# SmartSensorWifi.net
KiCad netlist of a schematic drawn in EAGLE
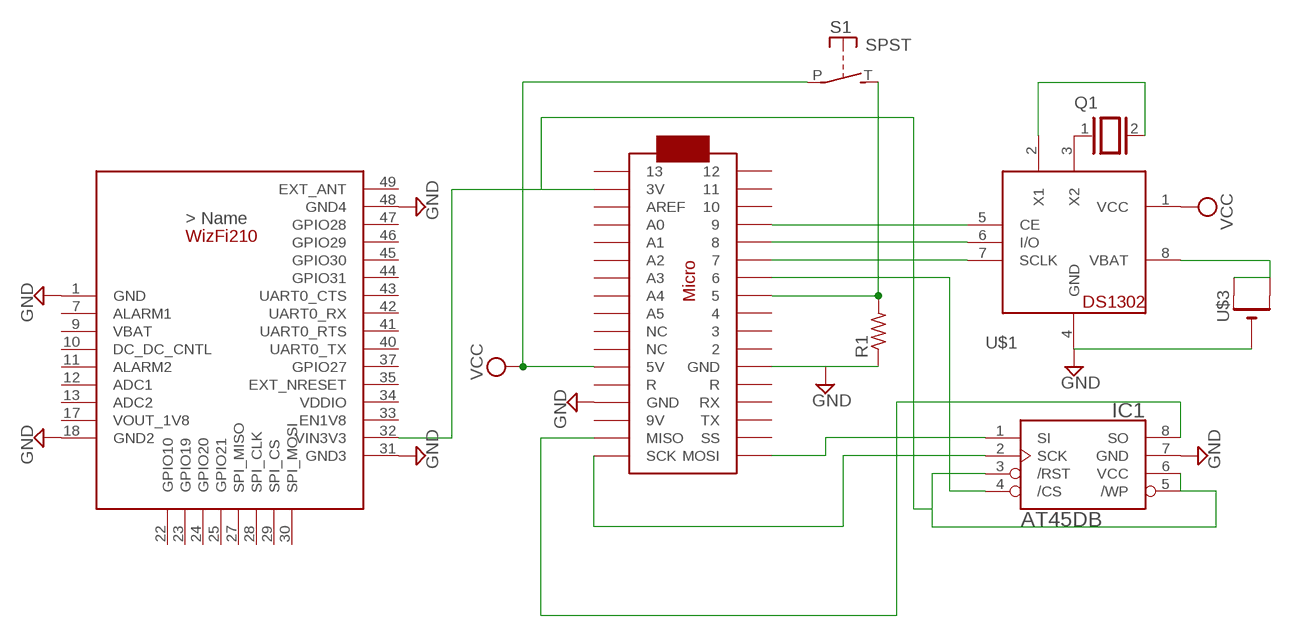
[diagram p0: schematic, sheet 1]

(export (version "E")
  (design (tool "Eeschema 10.0.6"))
  (components
    (comp (ref "IC1")
      (value "AT45DB-S")
      (footprint "eagle-import:SOIC8_208MIL")
      (libsource (lib "eagle-import") (part "AT45DB-S"))
    )
    (comp (ref "Q1")
      (value "XTAL")
      (footprint "eagle-import:Q")
      (libsource (lib "eagle-import") (part "XTAL"))
    )
    (comp (ref "R1")
      (value "FLIPFLOP-RES")
      (footprint "eagle-import:0805-THM")
      (libsource (lib "eagle-import") (part "FLIPFLOP-RES"))
    )
    (comp (ref "S1")
      (value "SPST")
      (footprint "eagle-import:JUDCOSPST")
      (libsource (lib "eagle-import") (part "SPST"))
    )
    (comp (ref "U$1")
      (value "DS1302")
      (footprint "eagle-import:DIL08-ROUND")
      (libsource (lib "eagle-import") (part "DS1302"))
    )
    (comp (ref "U$2")
      (value "ARDUINOMICRO")
      (footprint "eagle-import:ARDUINOMICRO")
      (libsource (lib "eagle-import") (part "ARDUINOMICRO"))
    )
    (comp (ref "U$3")
      (value "CR2032THM")
      (footprint "eagle-import:CR2032-THRU")
      (libsource (lib "eagle-import") (part "CR2032THM"))
    )
    (comp (ref "WIFI1")
      (value "WIZFI210")
      (footprint "eagle-import:WIZFI210")
      (libsource (lib "eagle-import") (part "WIZFI210"))
    )
  )
  (nets
    (net (code "1") (name "/VBAT") (class "Default")
      (node (ref "WIFI1") (pin "9") (pinfunction "VBAT_9") (pintype "power_in"))
    )
    (net (code "2") (name "/VOUT_1V8") (class "Default")
      (node (ref "WIFI1") (pin "17") (pinfunction "VOUT_1V8_17") (pintype "power_in"))
    )
    (net (code "3") (name "GND") (class "Default")
      (node (ref "IC1") (pin "7") (pinfunction "GND_7") (pintype "power_in"))
      (node (ref "R1") (pin "1") (pinfunction "1_1") (pintype "passive"))
      (node (ref "U$1") (pin "4") (pinfunction "GND_4") (pintype "power_in"))
      (node (ref "U$2") (pin "P$12") (pinfunction "GND_P$12") (pintype "bidirectional"))
      (node (ref "U$2") (pin "P$21") (pinfunction "GND_P$21") (pintype "bidirectional"))
      (node (ref "U$3") (pin "-") (pinfunction "-_-") (pintype "passive"))
      (node (ref "WIFI1") (pin "1") (pinfunction "GND_1") (pintype "power_in"))
      (node (ref "WIFI1") (pin "18") (pinfunction "GND2_18") (pintype "power_in"))
      (node (ref "WIFI1") (pin "31") (pinfunction "GND3_31") (pintype "power_in"))
      (node (ref "WIFI1") (pin "48") (pinfunction "GND4_48") (pintype "power_in"))
    )
    (net (code "4") (name "Net-(IC1-SCK)") (class "Default")
      (node (ref "IC1") (pin "2") (pinfunction "SCK_2") (pintype "input"))
      (node (ref "U$2") (pin "P$18") (pinfunction "SCK_P$18") (pintype "bidirectional"))
    )
    (net (code "5") (name "Net-(IC1-SI)") (class "Default")
      (node (ref "IC1") (pin "1") (pinfunction "SI_1") (pintype "input"))
      (node (ref "U$2") (pin "P$17") (pinfunction "MOSI_P$17") (pintype "bidirectional"))
    )
    (net (code "6") (name "Net-(IC1-SO)") (class "Default")
      (node (ref "IC1") (pin "8") (pinfunction "SO_8") (pintype "output"))
      (node (ref "U$2") (pin "P$19") (pinfunction "MISO_P$19") (pintype "bidirectional"))
    )
    (net (code "7") (name "Net-(IC1-VCC)") (class "Default")
      (node (ref "IC1") (pin "3") (pinfunction "/RST_3") (pintype "input"))
      (node (ref "IC1") (pin "5") (pinfunction "/WP_5") (pintype "input"))
      (node (ref "IC1") (pin "6") (pinfunction "VCC_6") (pintype "power_in"))
      (node (ref "U$2") (pin "P$33") (pinfunction "3V_P$33") (pintype "bidirectional"))
      (node (ref "WIFI1") (pin "32") (pinfunction "VIN3V3_32") (pintype "power_in"))
    )
    (net (code "8") (name "Net-(IC1-{slash}CS)") (class "Default")
      (node (ref "IC1") (pin "4") (pinfunction "/CS_4") (pintype "input"))
      (node (ref "U$2") (pin "P$7") (pinfunction "6_P$7") (pintype "bidirectional"))
    )
    (net (code "9") (name "Net-(S1-S)") (class "Default")
      (node (ref "R1") (pin "2") (pinfunction "2_2") (pintype "passive"))
      (node (ref "S1") (pin "T") (pinfunction "S_T") (pintype "passive"))
      (node (ref "U$2") (pin "P$8") (pinfunction "5_P$8") (pintype "bidirectional"))
    )
    (net (code "10") (name "Net-(U$1-CE)") (class "Default")
      (node (ref "U$1") (pin "5") (pinfunction "CE_5") (pintype "input"))
      (node (ref "U$2") (pin "P$4") (pinfunction "9_P$4") (pintype "bidirectional"))
    )
    (net (code "11") (name "Net-(U$1-I{slash}O)") (class "Default")
      (node (ref "U$1") (pin "6") (pinfunction "I/O_6") (pintype "bidirectional"))
      (node (ref "U$2") (pin "P$5") (pinfunction "8_P$5") (pintype "bidirectional"))
    )
    (net (code "12") (name "Net-(U$1-SCLK)") (class "Default")
      (node (ref "U$1") (pin "7") (pinfunction "SCLK_7") (pintype "input"))
      (node (ref "U$2") (pin "P$6") (pinfunction "7_P$6") (pintype "bidirectional"))
    )
    (net (code "13") (name "Net-(U$1-VBAT)") (class "Default")
      (node (ref "U$1") (pin "8") (pinfunction "VBAT_8") (pintype "power_in"))
      (node (ref "U$3") (pin "+1") (pinfunction "+_+1") (pintype "passive"))
      (node (ref "U$3") (pin "+2") (pinfunction "+1_+2") (pintype "passive"))
    )
    (net (code "14") (name "Net-(U$1-X1)") (class "Default")
      (node (ref "Q1") (pin "2") (pinfunction "2_2") (pintype "passive"))
      (node (ref "U$1") (pin "2") (pinfunction "X1_2") (pintype "passive"))
    )
    (net (code "15") (name "Net-(U$1-X2)") (class "Default")
      (node (ref "Q1") (pin "1") (pinfunction "1_1") (pintype "passive"))
      (node (ref "U$1") (pin "3") (pinfunction "X2_3") (pintype "passive"))
    )
    (net (code "16") (name "VCC") (class "Default")
      (node (ref "S1") (pin "P") (pinfunction "P_P") (pintype "passive"))
      (node (ref "U$1") (pin "1") (pinfunction "VCC_1") (pintype "power_in"))
      (node (ref "U$2") (pin "P$23") (pinfunction "5V_P$23") (pintype "bidirectional"))
    )
    (net (code "17") (name "unconnected-(U$2-2-PadP$11)") (class "Default")
      (node (ref "U$2") (pin "P$11") (pinfunction "2_P$11") (pintype "bidirectional"))
    )
    (net (code "18") (name "unconnected-(U$2-3-PadP$10)") (class "Default")
      (node (ref "U$2") (pin "P$10") (pinfunction "3_P$10") (pintype "bidirectional"))
    )
    (net (code "19") (name "unconnected-(U$2-4-PadP$9)") (class "Default")
      (node (ref "U$2") (pin "P$9") (pinfunction "4_P$9") (pintype "bidirectional"))
    )
    (net (code "20") (name "unconnected-(U$2-9V-PadP$20)") (class "Default")
      (node (ref "U$2") (pin "P$20") (pinfunction "9V_P$20") (pintype "bidirectional"))
    )
    (net (code "21") (name "unconnected-(U$2-10-PadP$3)") (class "Default")
      (node (ref "U$2") (pin "P$3") (pinfunction "10_P$3") (pintype "bidirectional"))
    )
    (net (code "22") (name "unconnected-(U$2-11-PadP$2)") (class "Default")
      (node (ref "U$2") (pin "P$2") (pinfunction "11_P$2") (pintype "bidirectional"))
    )
    (net (code "23") (name "unconnected-(U$2-12-PadP$1)") (class "Default")
      (node (ref "U$2") (pin "P$1") (pinfunction "12_P$1") (pintype "bidirectional"))
    )
    (net (code "24") (name "unconnected-(U$2-13-PadP$34)") (class "Default")
      (node (ref "U$2") (pin "P$34") (pinfunction "13_P$34") (pintype "bidirectional"))
    )
    (net (code "25") (name "unconnected-(U$2-A0-PadP$31)") (class "Default")
      (node (ref "U$2") (pin "P$31") (pinfunction "A0_P$31") (pintype "bidirectional"))
    )
    (net (code "26") (name "unconnected-(U$2-A1-PadP$30)") (class "Default")
      (node (ref "U$2") (pin "P$30") (pinfunction "A1_P$30") (pintype "bidirectional"))
    )
    (net (code "27") (name "unconnected-(U$2-A2-PadP$29)") (class "Default")
      (node (ref "U$2") (pin "P$29") (pinfunction "A2_P$29") (pintype "bidirectional"))
    )
    (net (code "28") (name "unconnected-(U$2-A3-PadP$28)") (class "Default")
      (node (ref "U$2") (pin "P$28") (pinfunction "A3_P$28") (pintype "bidirectional"))
    )
    (net (code "29") (name "unconnected-(U$2-A4-PadP$27)") (class "Default")
      (node (ref "U$2") (pin "P$27") (pinfunction "A4_P$27") (pintype "bidirectional"))
    )
    (net (code "30") (name "unconnected-(U$2-A5-PadP$26)") (class "Default")
      (node (ref "U$2") (pin "P$26") (pinfunction "A5_P$26") (pintype "bidirectional"))
    )
    (net (code "31") (name "unconnected-(U$2-AREF-PadP$32)") (class "Default")
      (node (ref "U$2") (pin "P$32") (pinfunction "AREF_P$32") (pintype "bidirectional"))
    )
    (net (code "32") (name "unconnected-(U$2-NC-PadP$24)") (class "Default")
      (node (ref "U$2") (pin "P$24") (pinfunction "NC_P$24") (pintype "bidirectional"))
    )
    (net (code "33") (name "unconnected-(U$2-NC-PadP$25)") (class "Default")
      (node (ref "U$2") (pin "P$25") (pinfunction "NC_P$25") (pintype "bidirectional"))
    )
    (net (code "34") (name "unconnected-(U$2-R-PadP$13)") (class "Default")
      (node (ref "U$2") (pin "P$13") (pinfunction "R_P$13") (pintype "bidirectional"))
    )
    (net (code "35") (name "unconnected-(U$2-R-PadP$22)") (class "Default")
      (node (ref "U$2") (pin "P$22") (pinfunction "R_P$22") (pintype "bidirectional"))
    )
    (net (code "36") (name "unconnected-(U$2-RX-PadP$14)") (class "Default")
      (node (ref "U$2") (pin "P$14") (pinfunction "RX_P$14") (pintype "bidirectional"))
    )
    (net (code "37") (name "unconnected-(U$2-SS-PadP$16)") (class "Default")
      (node (ref "U$2") (pin "P$16") (pinfunction "SS_P$16") (pintype "bidirectional"))
    )
    (net (code "38") (name "unconnected-(U$2-TX-PadP$15)") (class "Default")
      (node (ref "U$2") (pin "P$15") (pinfunction "TX_P$15") (pintype "bidirectional"))
    )
    (net (code "39") (name "unconnected-(WIFI1-ADC1-Pad12)") (class "Default")
      (node (ref "WIFI1") (pin "12") (pinfunction "ADC1_12") (pintype "input"))
    )
    (net (code "40") (name "unconnected-(WIFI1-ADC2-Pad13)") (class "Default")
      (node (ref "WIFI1") (pin "13") (pinfunction "ADC2_13") (pintype "input"))
    )
    (net (code "41") (name "unconnected-(WIFI1-ALARM1-Pad7)") (class "Default")
      (node (ref "WIFI1") (pin "7") (pinfunction "ALARM1_7") (pintype "input"))
    )
    (net (code "42") (name "unconnected-(WIFI1-ALARM2-Pad11)") (class "Default")
      (node (ref "WIFI1") (pin "11") (pinfunction "ALARM2_11") (pintype "bidirectional"))
    )
    (net (code "43") (name "unconnected-(WIFI1-DC_DC_CNTL-Pad10)") (class "Default")
      (node (ref "WIFI1") (pin "10") (pinfunction "DC_DC_CNTL_10") (pintype "output"))
    )
    (net (code "44") (name "unconnected-(WIFI1-EN1V8-Pad33)") (class "Default")
      (node (ref "WIFI1") (pin "33") (pinfunction "EN1V8_33") (pintype "bidirectional"))
    )
    (net (code "45") (name "unconnected-(WIFI1-EXT_ANT-Pad49)") (class "Default")
      (node (ref "WIFI1") (pin "49") (pinfunction "EXT_ANT_49") (pintype "bidirectional"))
    )
    (net (code "46") (name "unconnected-(WIFI1-EXT_NRESET-Pad35)") (class "Default")
      (node (ref "WIFI1") (pin "35") (pinfunction "EXT_NRESET_35") (pintype "bidirectional"))
    )
    (net (code "47") (name "unconnected-(WIFI1-GPIO10-Pad22)") (class "Default")
      (node (ref "WIFI1") (pin "22") (pinfunction "GPIO10_22") (pintype "bidirectional"))
    )
    (net (code "48") (name "unconnected-(WIFI1-GPIO19-Pad23)") (class "Default")
      (node (ref "WIFI1") (pin "23") (pinfunction "GPIO19_23") (pintype "bidirectional"))
    )
    (net (code "49") (name "unconnected-(WIFI1-GPIO20-Pad24)") (class "Default")
      (node (ref "WIFI1") (pin "24") (pinfunction "GPIO20_24") (pintype "bidirectional"))
    )
    (net (code "50") (name "unconnected-(WIFI1-GPIO21-Pad25)") (class "Default")
      (node (ref "WIFI1") (pin "25") (pinfunction "GPIO21_25") (pintype "bidirectional"))
    )
    (net (code "51") (name "unconnected-(WIFI1-GPIO27-Pad37)") (class "Default")
      (node (ref "WIFI1") (pin "37") (pinfunction "GPIO27_37") (pintype "bidirectional"))
    )
    (net (code "52") (name "unconnected-(WIFI1-GPIO28-Pad47)") (class "Default")
      (node (ref "WIFI1") (pin "47") (pinfunction "GPIO28_47") (pintype "bidirectional"))
    )
    (net (code "53") (name "unconnected-(WIFI1-GPIO29-Pad46)") (class "Default")
      (node (ref "WIFI1") (pin "46") (pinfunction "GPIO29_46") (pintype "bidirectional"))
    )
    (net (code "54") (name "unconnected-(WIFI1-GPIO30-Pad45)") (class "Default")
      (node (ref "WIFI1") (pin "45") (pinfunction "GPIO30_45") (pintype "bidirectional"))
    )
    (net (code "55") (name "unconnected-(WIFI1-GPIO31-Pad44)") (class "Default")
      (node (ref "WIFI1") (pin "44") (pinfunction "GPIO31_44") (pintype "bidirectional"))
    )
    (net (code "56") (name "unconnected-(WIFI1-SPI_CLK-Pad28)") (class "Default")
      (node (ref "WIFI1") (pin "28") (pinfunction "SPI_CLK_28") (pintype "input"))
    )
    (net (code "57") (name "unconnected-(WIFI1-SPI_CS-Pad29)") (class "Default")
      (node (ref "WIFI1") (pin "29") (pinfunction "SPI_CS_29") (pintype "input"))
    )
    (net (code "58") (name "unconnected-(WIFI1-SPI_MISO-Pad27)") (class "Default")
      (node (ref "WIFI1") (pin "27") (pinfunction "SPI_MISO_27") (pintype "output"))
    )
    (net (code "59") (name "unconnected-(WIFI1-SPI_MOSI-Pad30)") (class "Default")
      (node (ref "WIFI1") (pin "30") (pinfunction "SPI_MOSI_30") (pintype "input"))
    )
    (net (code "60") (name "unconnected-(WIFI1-UART0_CTS-Pad43)") (class "Default")
      (node (ref "WIFI1") (pin "43") (pinfunction "UART0_CTS_43") (pintype "bidirectional"))
    )
    (net (code "61") (name "unconnected-(WIFI1-UART0_RTS-Pad41)") (class "Default")
      (node (ref "WIFI1") (pin "41") (pinfunction "UART0_RTS_41") (pintype "bidirectional"))
    )
    (net (code "62") (name "unconnected-(WIFI1-UART0_RX-Pad42)") (class "Default")
      (node (ref "WIFI1") (pin "42") (pinfunction "UART0_RX_42") (pintype "bidirectional"))
    )
    (net (code "63") (name "unconnected-(WIFI1-UART0_TX-Pad40)") (class "Default")
      (node (ref "WIFI1") (pin "40") (pinfunction "UART0_TX_40") (pintype "bidirectional"))
    )
    (net (code "64") (name "unconnected-(WIFI1-VDDIO-Pad34)") (class "Default")
      (node (ref "WIFI1") (pin "34") (pinfunction "VDDIO_34") (pintype "bidirectional"))
    )
  )
)
